# SoftCore_SA_P4.net
KiCad netlist of a schematic drawn in Altium Designer
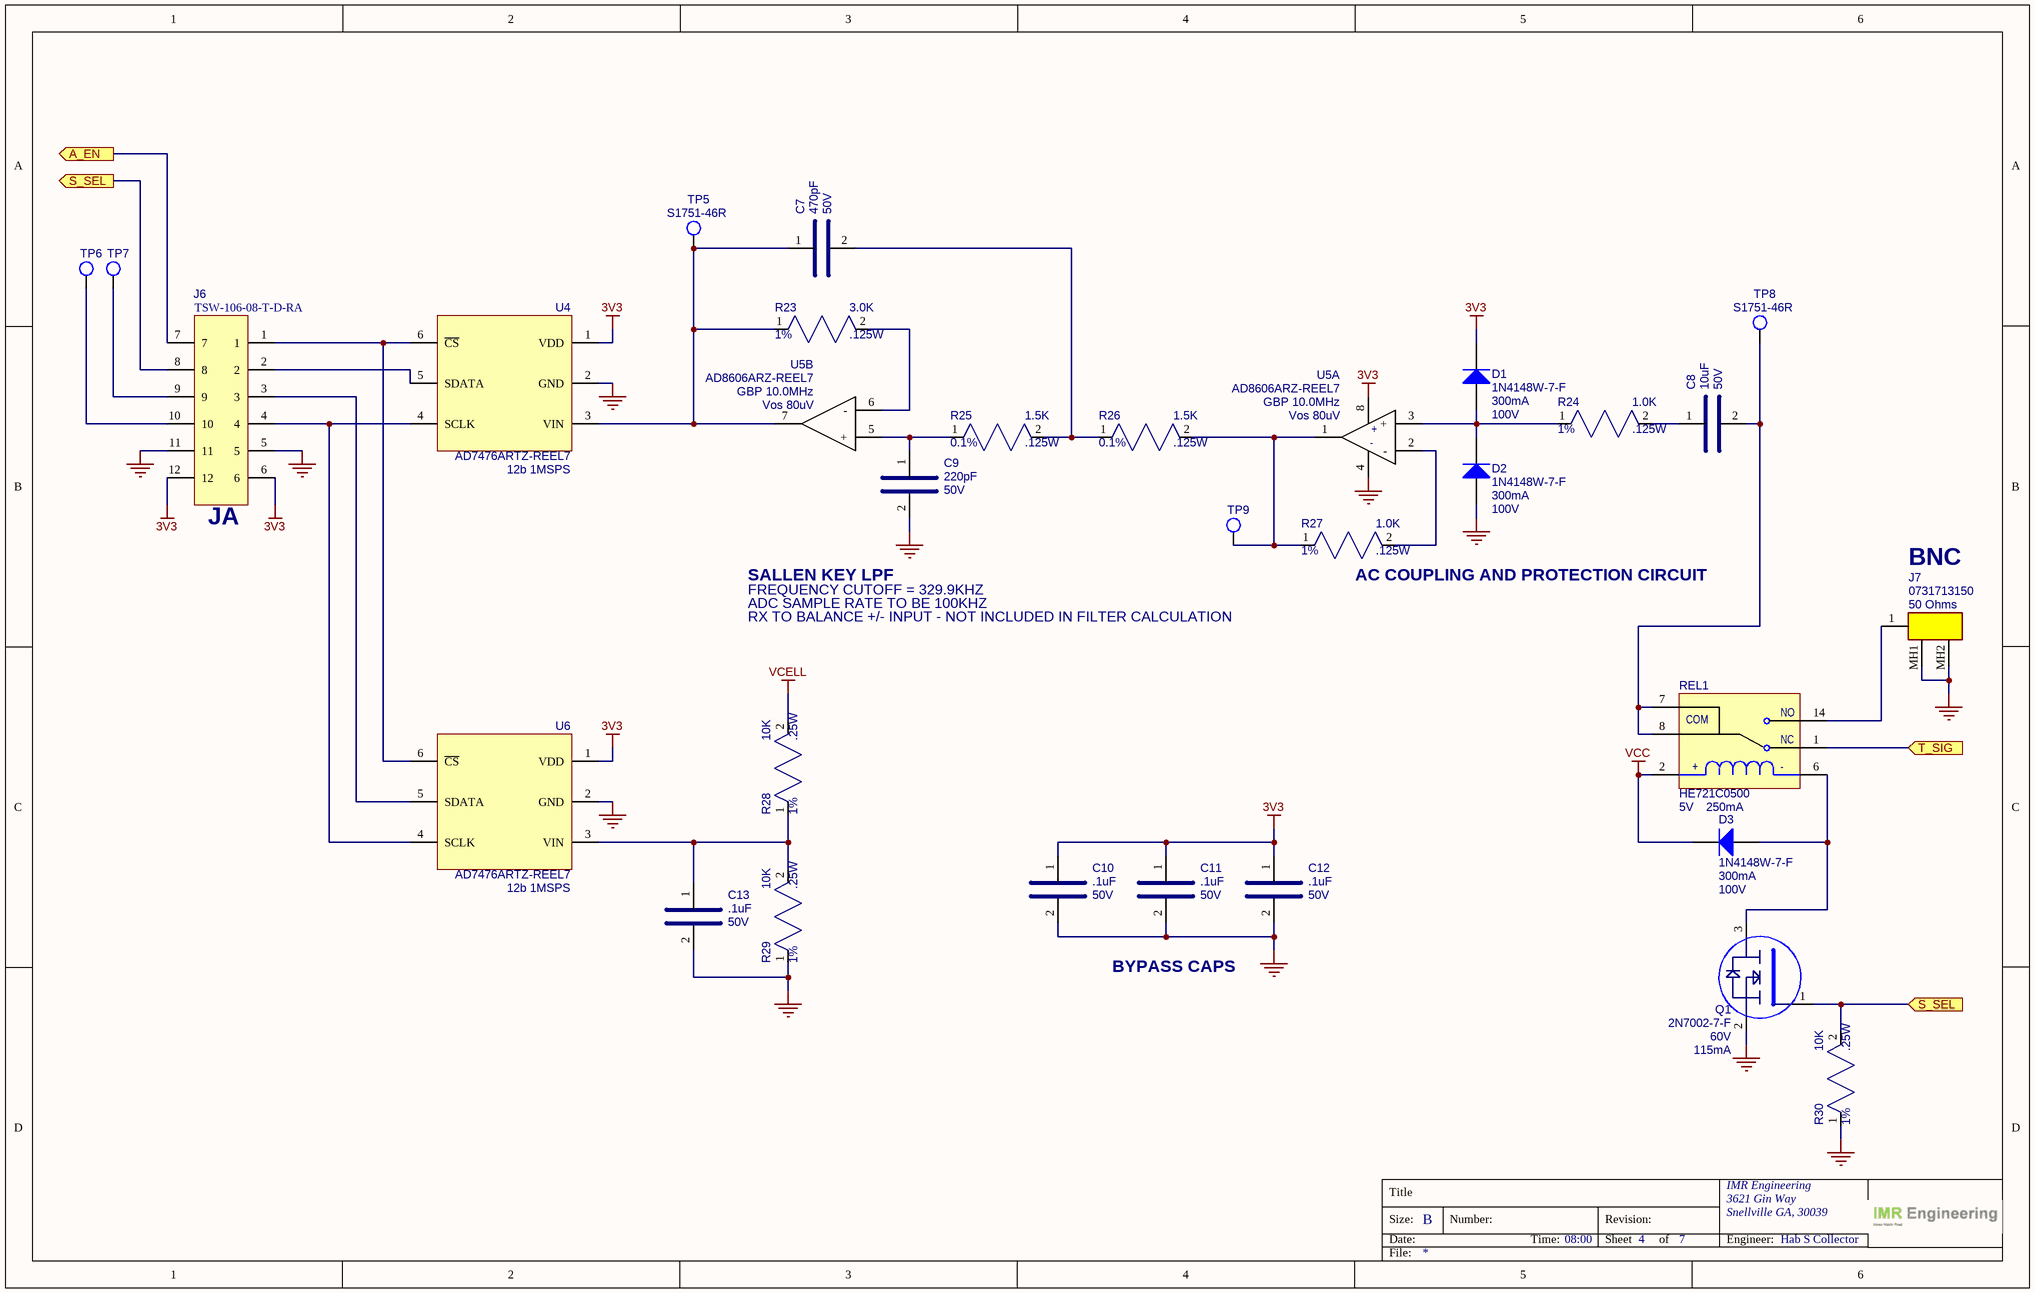
[diagram p0: SoftCore_SA_P4.SchDoc]

(export (version "E")
  (design (tool "Eeschema 10.0.6"))
  (components
    (comp (ref "C7")
      (value "470pF")
      (footprint "CAP_0805")
      (description "CAP CER 470PF 50V COG/NP0 0805")
      (fields (field (name "MFG") "Yageo") (field (name "TOLERANCE") "5%") (field (name "VOLTAGE") "50V"))
      (libsource (lib "IMR_LIB_SCH_R2") (part "CAP_SMD_470PF_50V_0805"))
    )
    (comp (ref "C8")
      (value "10uF")
      (footprint "CAP_0805")
      (description "CAP CER 10UF 50V X5R 0805")
      (fields
        (field (name "MFG") "Murata Electronics")
        (field (name "VOLTAGE") "50V")
        (field (name "Comment") "GRM21BR61H106KE43L")
      )
      (libsource (lib "IMR_LIB_SCH_R2") (part "CAP_SMD_10UF_50V_0805"))
    )
    (comp (ref "C9")
      (value "220pF")
      (footprint "CAP_0805")
      (description "CAP CER 220PF 50V COG/NP0 0805")
      (fields (field (name "MFG") "Yageo") (field (name "TOLERANCE") "5%") (field (name "VOLTAGE") "50V"))
      (libsource (lib "IMR_LIB_SCH_R2") (part "CAP_SMD_220PF_50V_0805"))
    )
    (comp (ref "C10")
      (value ".1uF")
      (footprint "CAP_0805")
      (description "CAP CER 0.1UF 50V X7R 0805")
      (fields
        (field (name "MFG") "KYOCERA AVX")
        (field (name "VOLTAGE") "50V")
        (field (name "Comment") "KGM21NR71H104KT")
      )
      (libsource (lib "IMR_LIB_SCH_R2") (part "CAP_SMD_0.1UF_50V_0805"))
    )
    (comp (ref "C11")
      (value ".1uF")
      (footprint "CAP_0805")
      (description "CAP CER 0.1UF 50V X7R 0805")
      (fields
        (field (name "MFG") "KYOCERA AVX")
        (field (name "VOLTAGE") "50V")
        (field (name "Comment") "KGM21NR71H104KT")
      )
      (libsource (lib "IMR_LIB_SCH_R2") (part "CAP_SMD_0.1UF_50V_0805"))
    )
    (comp (ref "C12")
      (value ".1uF")
      (footprint "CAP_0805")
      (description "CAP CER 0.1UF 50V X7R 0805")
      (fields
        (field (name "MFG") "KYOCERA AVX")
        (field (name "VOLTAGE") "50V")
        (field (name "Comment") "KGM21NR71H104KT")
      )
      (libsource (lib "IMR_LIB_SCH_R2") (part "CAP_SMD_0.1UF_50V_0805"))
    )
    (comp (ref "C13")
      (value ".1uF")
      (footprint "CAP_0805")
      (description "CAP CER 0.1UF 50V X7R 0805")
      (fields
        (field (name "MFG") "KYOCERA AVX")
        (field (name "VOLTAGE") "50V")
        (field (name "Comment") "KGM21NR71H104KT")
      )
      (libsource (lib "IMR_LIB_SCH_R2") (part "CAP_SMD_0.1UF_50V_0805"))
    )
    (comp (ref "D1")
      (value "100V")
      (footprint "SOD123")
      (description "RELAY REED SPDT 250MA 5V")
      (fields
        (field (name "MFG") "Diodes Inc")
        (field (name "MFG_PN") "1N4148W-7-F")
        (field (name "CURRENT") "300mA")
        (field (name "Comment") "1N4148W-7-F")
      )
      (libsource (lib "IMR_LIB_SCH_R2") (part "DIODE_1N4148W-7-F"))
    )
    (comp (ref "D2")
      (value "100V")
      (footprint "SOD123")
      (description "RELAY REED SPDT 250MA 5V")
      (fields
        (field (name "MFG") "Diodes Inc")
        (field (name "MFG_PN") "1N4148W-7-F")
        (field (name "CURRENT") "300mA")
        (field (name "Comment") "1N4148W-7-F")
      )
      (libsource (lib "IMR_LIB_SCH_R2") (part "DIODE_1N4148W-7-F"))
    )
    (comp (ref "D3")
      (value "100V")
      (footprint "SOD123")
      (description "RELAY REED SPDT 250MA 5V")
      (fields
        (field (name "MFG") "Diodes Inc")
        (field (name "MFG_PN") "1N4148W-7-F")
        (field (name "CURRENT") "300mA")
        (field (name "Comment") "1N4148W-7-F")
      )
      (libsource (lib "IMR_LIB_SCH_R2") (part "DIODE_1N4148W-7-F"))
    )
    (comp (ref "J6")
      (value "TSW-106-08-T-D-RA")
      (footprint "SAMTEC_TSW-106-08-T-D-RA")
      (description "CONN HEADER R/A 12POS 2.54MM")
      (fields (field (name "MFG") "Samtec Inc.") (field (name "MFG_PN") "TSW-106-08-T-D-RA"))
      (libsource (lib "IMR_LIB_SCH_R2") (part "CONN_HEADER_12P_100MIL_RA"))
    )
    (comp (ref "J7")
      (value "50 Ohms")
      (footprint "731713150")
      (description "CONN BNC RCPT R/A 50 OHM PCB")
      (fields
        (field (name "MFG") "Molex")
        (field (name "MFG_PN") "0731713150")
        (field (name "Comment") "0731713150")
      )
      (libsource (lib "IMR_LIB_SCH_R2") (part "CONN_MOLEX_0731713150"))
    )
    (comp (ref "Q1")
      (value "60V")
      (footprint "SOT-23")
      (description "MOSFET N-CH 60V 115MA SOT23-3")
      (fields
        (field (name "MFG") "Diodes Inc")
        (field (name "MFG_PN") "2N7002-7-F")
        (field (name "CURRENT") "115mA")
        (field (name "Comment") "2N7002-7-F")
      )
      (libsource (lib "IMR_LIB_SCH_R2") (part "MOSFET_NCH_2N7002-7-F"))
    )
    (comp (ref "R23")
      (value "3.0K")
      (footprint "RES_0805")
      (description "RES SMD 3.0K OHM 1% 1/8W 0805")
      (fields
        (field (name "MFG") "Yageo")
        (field (name "POWER") ".125W")
        (field (name "TOLERANCE") "1%")
        (field (name "Comment") "RC0805FR-133KL")
      )
      (libsource (lib "IMR_LIB_SCH_R2") (part "RES_SMD_3.0K_0805_1/8W_1%"))
    )
    (comp (ref "R24")
      (value "1.0K")
      (footprint "RES_0805")
      (description "RES SMD 1.0K OHM 1% 1/8W 0805")
      (fields
        (field (name "MFG") "Yageo")
        (field (name "POWER") ".125W")
        (field (name "TOLERANCE") "1%")
        (field (name "Comment") "RC0805FR-071KL")
      )
      (libsource (lib "IMR_LIB_SCH_R2") (part "RES_SMD_1.0K_0805_1/8W_1%"))
    )
    (comp (ref "R25")
      (value "1.5K")
      (footprint "RES_0805")
      (description "RES SMD 1.5K OHM 0.1% 1/8W 0805")
      (fields
        (field (name "MFG") "Yageo")
        (field (name "POWER") ".125W")
        (field (name "TOLERANCE") "0.1%")
        (field (name "Comment") "RT0805BRD071K5L")
      )
      (libsource (lib "IMR_LIB_SCH_R2") (part "RES_SMD_1.5K_0805_1/8W_0.1%"))
    )
    (comp (ref "R26")
      (value "1.5K")
      (footprint "RES_0805")
      (description "RES SMD 1.5K OHM 0.1% 1/8W 0805")
      (fields
        (field (name "MFG") "Yageo")
        (field (name "POWER") ".125W")
        (field (name "TOLERANCE") "0.1%")
        (field (name "Comment") "RT0805BRD071K5L")
      )
      (libsource (lib "IMR_LIB_SCH_R2") (part "RES_SMD_1.5K_0805_1/8W_0.1%"))
    )
    (comp (ref "R27")
      (value "1.0K")
      (footprint "RES_0805")
      (description "RES SMD 1.0K OHM 1% 1/8W 0805")
      (fields
        (field (name "MFG") "Yageo")
        (field (name "POWER") ".125W")
        (field (name "TOLERANCE") "1%")
        (field (name "Comment") "RC0805FR-071KL")
      )
      (libsource (lib "IMR_LIB_SCH_R2") (part "RES_SMD_1.0K_0805_1/8W_1%"))
    )
    (comp (ref "R28")
      (value "10K")
      (footprint "RES_0805")
      (description "RES SMD 10K OHM 1% 1/4W 0805")
      (fields
        (field (name "MFG") "Yageo")
        (field (name "POWER") ".25W")
        (field (name "TOLERANCE") "1%")
        (field (name "Comment") "RC0805FR-7W10KL")
      )
      (libsource (lib "IMR_LIB_SCH_R2") (part "RES_SMD_10K_0805_1/4W_1%"))
    )
    (comp (ref "R29")
      (value "10K")
      (footprint "RES_0805")
      (description "RES SMD 10K OHM 1% 1/4W 0805")
      (fields
        (field (name "MFG") "Yageo")
        (field (name "POWER") ".25W")
        (field (name "TOLERANCE") "1%")
        (field (name "Comment") "RC0805FR-7W10KL")
      )
      (libsource (lib "IMR_LIB_SCH_R2") (part "RES_SMD_10K_0805_1/4W_1%"))
    )
    (comp (ref "R30")
      (value "10K")
      (footprint "RES_0805")
      (description "RES SMD 10K OHM 1% 1/4W 0805")
      (fields
        (field (name "MFG") "Yageo")
        (field (name "POWER") ".25W")
        (field (name "TOLERANCE") "1%")
        (field (name "Comment") "RC0805FR-7W10KL")
      )
      (libsource (lib "IMR_LIB_SCH_R2") (part "RES_SMD_10K_0805_1/4W_1%"))
    )
    (comp (ref "REL1")
      (value "5V")
      (footprint "HE700")
      (description "RELAY REED SPDT 250MA 5V")
      (fields
        (field (name "MFG") "Littlefuse")
        (field (name "MFG_PN") "HE721C0500")
        (field (name "CURRENT") "250mA")
        (field (name "Comment") "HE721C0500")
      )
      (libsource (lib "IMR_LIB_SCH_R2") (part "RELAY_HE721C0500"))
    )
    (comp (ref "TP5")
      (value "S1751-46R")
      (footprint "HARWIN_S1751")
      (description "PCB TEST POINT CONNECT")
      (fields (field (name "MFG") "Harwin Inc") (field (name "MFG_PN") "S1751-46R"))
      (libsource (lib "IMR_LIB_SCH_R2") (part "CONN_TEST_POINT_S1751-46R"))
    )
    (comp (ref "TP6")
      (value "~")
      (footprint "TEST_POINT_20MIL_TH")
      (description "TEST POINT TH 20MIL HOLE")
      (libsource (lib "IMR_LIB_SCH_R2") (part "CONN_TEST_POINT_TH_PAD_20MIL"))
    )
    (comp (ref "TP7")
      (value "~")
      (footprint "TEST_POINT_20MIL_TH")
      (description "TEST POINT TH 20MIL HOLE")
      (libsource (lib "IMR_LIB_SCH_R2") (part "CONN_TEST_POINT_TH_PAD_20MIL"))
    )
    (comp (ref "TP8")
      (value "S1751-46R")
      (footprint "HARWIN_S1751")
      (description "PCB TEST POINT CONNECT")
      (fields (field (name "MFG") "Harwin Inc") (field (name "MFG_PN") "S1751-46R"))
      (libsource (lib "IMR_LIB_SCH_R2") (part "CONN_TEST_POINT_S1751-46R"))
    )
    (comp (ref "TP9")
      (value "~")
      (footprint "TEST_POINT_20MIL_TH")
      (description "TEST POINT TH 20MIL HOLE")
      (libsource (lib "IMR_LIB_SCH_R2") (part "CONN_TEST_POINT_TH_PAD_20MIL"))
    )
    (comp (ref "U4")
      (value "12b 1MSPS")
      (footprint "SOT-23-6")
      (description "IC ADC 12BIT SAR SOT23-6")
      (fields
        (field (name "MFG") "Analog Devices")
        (field (name "MFG_PN") "AD7476ARTZ-REEL7")
        (field (name "Comment") "AD7476ARTZ-REEL7")
      )
      (libsource (lib "IMR_LIB_SCH_R2") (part "IC_AD7476ARTZ-REEL7"))
    )
    (comp (ref "U5")
      (value "GBP 10.0MHz")
      (footprint "SOIC-8_54")
      (description "IC OPAMP GP 2 CIRCUIT 8SOIC")
      (fields
        (field (name "MFG") "Analog Devices")
        (field (name "MFG_PN") "AD8606ARZ-REEL7")
        (field (name "VOS") "Vos 80uV")
        (field (name "Comment") "AD8606ARZ-REEL7")
      )
      (libsource (lib "IMR_LIB_SCH_R2") (part "IC_OPAMP_AD8606ARZ-REEL7"))
    )
    (comp (ref "U6")
      (value "12b 1MSPS")
      (footprint "SOT-23-6")
      (description "IC ADC 12BIT SAR SOT23-6")
      (fields
        (field (name "MFG") "Analog Devices")
        (field (name "MFG_PN") "AD7476ARTZ-REEL7")
        (field (name "Comment") "AD7476ARTZ-REEL7")
      )
      (libsource (lib "IMR_LIB_SCH_R2") (part "IC_AD7476ARTZ-REEL7"))
    )
  )
  (nets
    (net (code "1") (name "/A_EN") (class "Default")
      (node (ref "J6") (pin "7") (pinfunction "7_7") (pintype "passive"))
    )
    (net (code "2") (name "/S_SEL") (class "Default")
      (node (ref "J6") (pin "8") (pinfunction "8_8") (pintype "passive"))
      (node (ref "Q1") (pin "1") (pinfunction "B_1") (pintype "passive"))
      (node (ref "R30") (pin "2") (pinfunction "2_2") (pintype "passive"))
    )
    (net (code "3") (name "/T_SIG") (class "Default")
      (node (ref "REL1") (pin "1") (pinfunction "NC_1") (pintype "passive"))
    )
    (net (code "4") (name "3V3") (class "Default")
      (node (ref "C10") (pin "1") (pinfunction "1_1") (pintype "passive"))
      (node (ref "C11") (pin "1") (pinfunction "1_1") (pintype "passive"))
      (node (ref "C12") (pin "1") (pinfunction "1_1") (pintype "passive"))
      (node (ref "D1") (pin "2") (pinfunction "K_2") (pintype "passive"))
      (node (ref "J6") (pin "12") (pinfunction "12_12") (pintype "passive"))
      (node (ref "J6") (pin "6") (pinfunction "6_6") (pintype "passive"))
      (node (ref "U4") (pin "1") (pinfunction "VDD_1") (pintype "passive"))
      (node (ref "U5") (pin "8") (pintype "passive"))
      (node (ref "U6") (pin "1") (pinfunction "VDD_1") (pintype "passive"))
    )
    (net (code "5") (name "GND") (class "Default")
      (node (ref "C10") (pin "2") (pinfunction "2_2") (pintype "passive"))
      (node (ref "C11") (pin "2") (pinfunction "2_2") (pintype "passive"))
      (node (ref "C12") (pin "2") (pinfunction "2_2") (pintype "passive"))
      (node (ref "C13") (pin "2") (pinfunction "2_2") (pintype "passive"))
      (node (ref "C9") (pin "2") (pinfunction "2_2") (pintype "passive"))
      (node (ref "D2") (pin "1") (pinfunction "A_1") (pintype "passive"))
      (node (ref "J6") (pin "11") (pinfunction "11_11") (pintype "passive"))
      (node (ref "J6") (pin "5") (pinfunction "5_5") (pintype "passive"))
      (node (ref "J7") (pin "MH1") (pintype "passive"))
      (node (ref "J7") (pin "MH2") (pintype "passive"))
      (node (ref "Q1") (pin "2") (pinfunction "E_2") (pintype "passive"))
      (node (ref "R29") (pin "1") (pinfunction "1_1") (pintype "passive"))
      (node (ref "R30") (pin "1") (pinfunction "1_1") (pintype "passive"))
      (node (ref "U4") (pin "2") (pinfunction "GND_2") (pintype "passive"))
      (node (ref "U5") (pin "4") (pintype "passive"))
      (node (ref "U6") (pin "2") (pinfunction "GND_2") (pintype "passive"))
    )
    (net (code "6") (name "Net-(C7-Pad2)") (class "Default")
      (node (ref "C7") (pin "2") (pinfunction "2_2") (pintype "passive"))
      (node (ref "R25") (pin "2") (pinfunction "2_2") (pintype "passive"))
      (node (ref "R26") (pin "1") (pinfunction "1_1") (pintype "passive"))
    )
    (net (code "7") (name "Net-(C8-Pad1)") (class "Default")
      (node (ref "C8") (pin "1") (pinfunction "1_1") (pintype "passive"))
      (node (ref "R24") (pin "2") (pinfunction "2_2") (pintype "passive"))
    )
    (net (code "8") (name "Net-(C8-Pad2)") (class "Default")
      (node (ref "C8") (pin "2") (pinfunction "2_2") (pintype "passive"))
      (node (ref "REL1") (pin "7") (pinfunction "COM_7") (pintype "passive"))
      (node (ref "REL1") (pin "8") (pinfunction "COM_8") (pintype "passive"))
      (node (ref "TP8") (pin "1") (pintype "passive"))
    )
    (net (code "9") (name "Net-(D1-A)") (class "Default")
      (node (ref "D1") (pin "1") (pinfunction "A_1") (pintype "passive"))
      (node (ref "D2") (pin "2") (pinfunction "K_2") (pintype "passive"))
      (node (ref "R24") (pin "1") (pinfunction "1_1") (pintype "passive"))
      (node (ref "U5") (pin "3") (pinfunction "+_3") (pintype "passive"))
    )
    (net (code "10") (name "Net-(D3-A)") (class "Default")
      (node (ref "D3") (pin "1") (pinfunction "A_1") (pintype "passive"))
      (node (ref "Q1") (pin "3") (pinfunction "C_3") (pintype "passive"))
      (node (ref "REL1") (pin "6") (pintype "passive"))
    )
    (net (code "11") (name "Net-(J6-Pad9)") (class "Default")
      (node (ref "J6") (pin "9") (pinfunction "9_9") (pintype "passive"))
      (node (ref "TP7") (pin "1") (pintype "passive"))
    )
    (net (code "12") (name "Net-(J6-Pad10)") (class "Default")
      (node (ref "J6") (pin "10") (pinfunction "10_10") (pintype "passive"))
      (node (ref "TP6") (pin "1") (pintype "passive"))
    )
    (net (code "13") (name "Net-(R26-Pad2)") (class "Default")
      (node (ref "R26") (pin "2") (pinfunction "2_2") (pintype "passive"))
      (node (ref "R27") (pin "1") (pinfunction "1_1") (pintype "passive"))
      (node (ref "TP9") (pin "1") (pintype "passive"))
      (node (ref "U5") (pin "1") (pintype "passive"))
    )
    (net (code "14") (name "Net-(REL1-NO)") (class "Default")
      (node (ref "J7") (pin "1") (pintype "passive"))
      (node (ref "REL1") (pin "14") (pinfunction "NO_14") (pintype "passive"))
    )
    (net (code "15") (name "Net-(U4-SCLK)") (class "Default")
      (node (ref "J6") (pin "4") (pinfunction "4_4") (pintype "passive"))
      (node (ref "U4") (pin "4") (pinfunction "SCLK_4") (pintype "passive"))
      (node (ref "U6") (pin "4") (pinfunction "SCLK_4") (pintype "passive"))
    )
    (net (code "16") (name "Net-(U4-SDATA)") (class "Default")
      (node (ref "J6") (pin "2") (pinfunction "2_2") (pintype "passive"))
      (node (ref "U4") (pin "5") (pinfunction "SDATA_5") (pintype "passive"))
    )
    (net (code "17") (name "Net-(U4-VIN)") (class "Default")
      (node (ref "C7") (pin "1") (pinfunction "1_1") (pintype "passive"))
      (node (ref "R23") (pin "1") (pinfunction "1_1") (pintype "passive"))
      (node (ref "TP5") (pin "1") (pintype "passive"))
      (node (ref "U4") (pin "3") (pinfunction "VIN_3") (pintype "passive"))
      (node (ref "U5") (pin "7") (pintype "passive"))
    )
    (net (code "18") (name "Net-(U4-~{CS})") (class "Default")
      (node (ref "J6") (pin "1") (pinfunction "1_1") (pintype "passive"))
      (node (ref "U4") (pin "6") (pinfunction "~{CS}_6") (pintype "passive"))
      (node (ref "U6") (pin "6") (pinfunction "~{CS}_6") (pintype "passive"))
    )
    (net (code "19") (name "Net-(U5A--)") (class "Default")
      (node (ref "R27") (pin "2") (pinfunction "2_2") (pintype "passive"))
      (node (ref "U5") (pin "2") (pinfunction "-_2") (pintype "passive"))
    )
    (net (code "20") (name "Net-(U5B-+)") (class "Default")
      (node (ref "C9") (pin "1") (pinfunction "1_1") (pintype "passive"))
      (node (ref "R25") (pin "1") (pinfunction "1_1") (pintype "passive"))
      (node (ref "U5") (pin "5") (pinfunction "+_5") (pintype "passive"))
    )
    (net (code "21") (name "Net-(U5B--)") (class "Default")
      (node (ref "R23") (pin "2") (pinfunction "2_2") (pintype "passive"))
      (node (ref "U5") (pin "6") (pinfunction "-_6") (pintype "passive"))
    )
    (net (code "22") (name "Net-(U6-SDATA)") (class "Default")
      (node (ref "J6") (pin "3") (pinfunction "3_3") (pintype "passive"))
      (node (ref "U6") (pin "5") (pinfunction "SDATA_5") (pintype "passive"))
    )
    (net (code "23") (name "Net-(U6-VIN)") (class "Default")
      (node (ref "C13") (pin "1") (pinfunction "1_1") (pintype "passive"))
      (node (ref "R28") (pin "1") (pinfunction "1_1") (pintype "passive"))
      (node (ref "R29") (pin "2") (pinfunction "2_2") (pintype "passive"))
      (node (ref "U6") (pin "3") (pinfunction "VIN_3") (pintype "passive"))
    )
    (net (code "24") (name "VCC") (class "Default")
      (node (ref "D3") (pin "2") (pinfunction "K_2") (pintype "passive"))
      (node (ref "REL1") (pin "2") (pintype "passive"))
    )
    (net (code "25") (name "VCELL") (class "Default")
      (node (ref "R28") (pin "2") (pinfunction "2_2") (pintype "passive"))
    )
  )
)
